# seletor.net
KiCad netlist of a schematic drawn in EAGLE
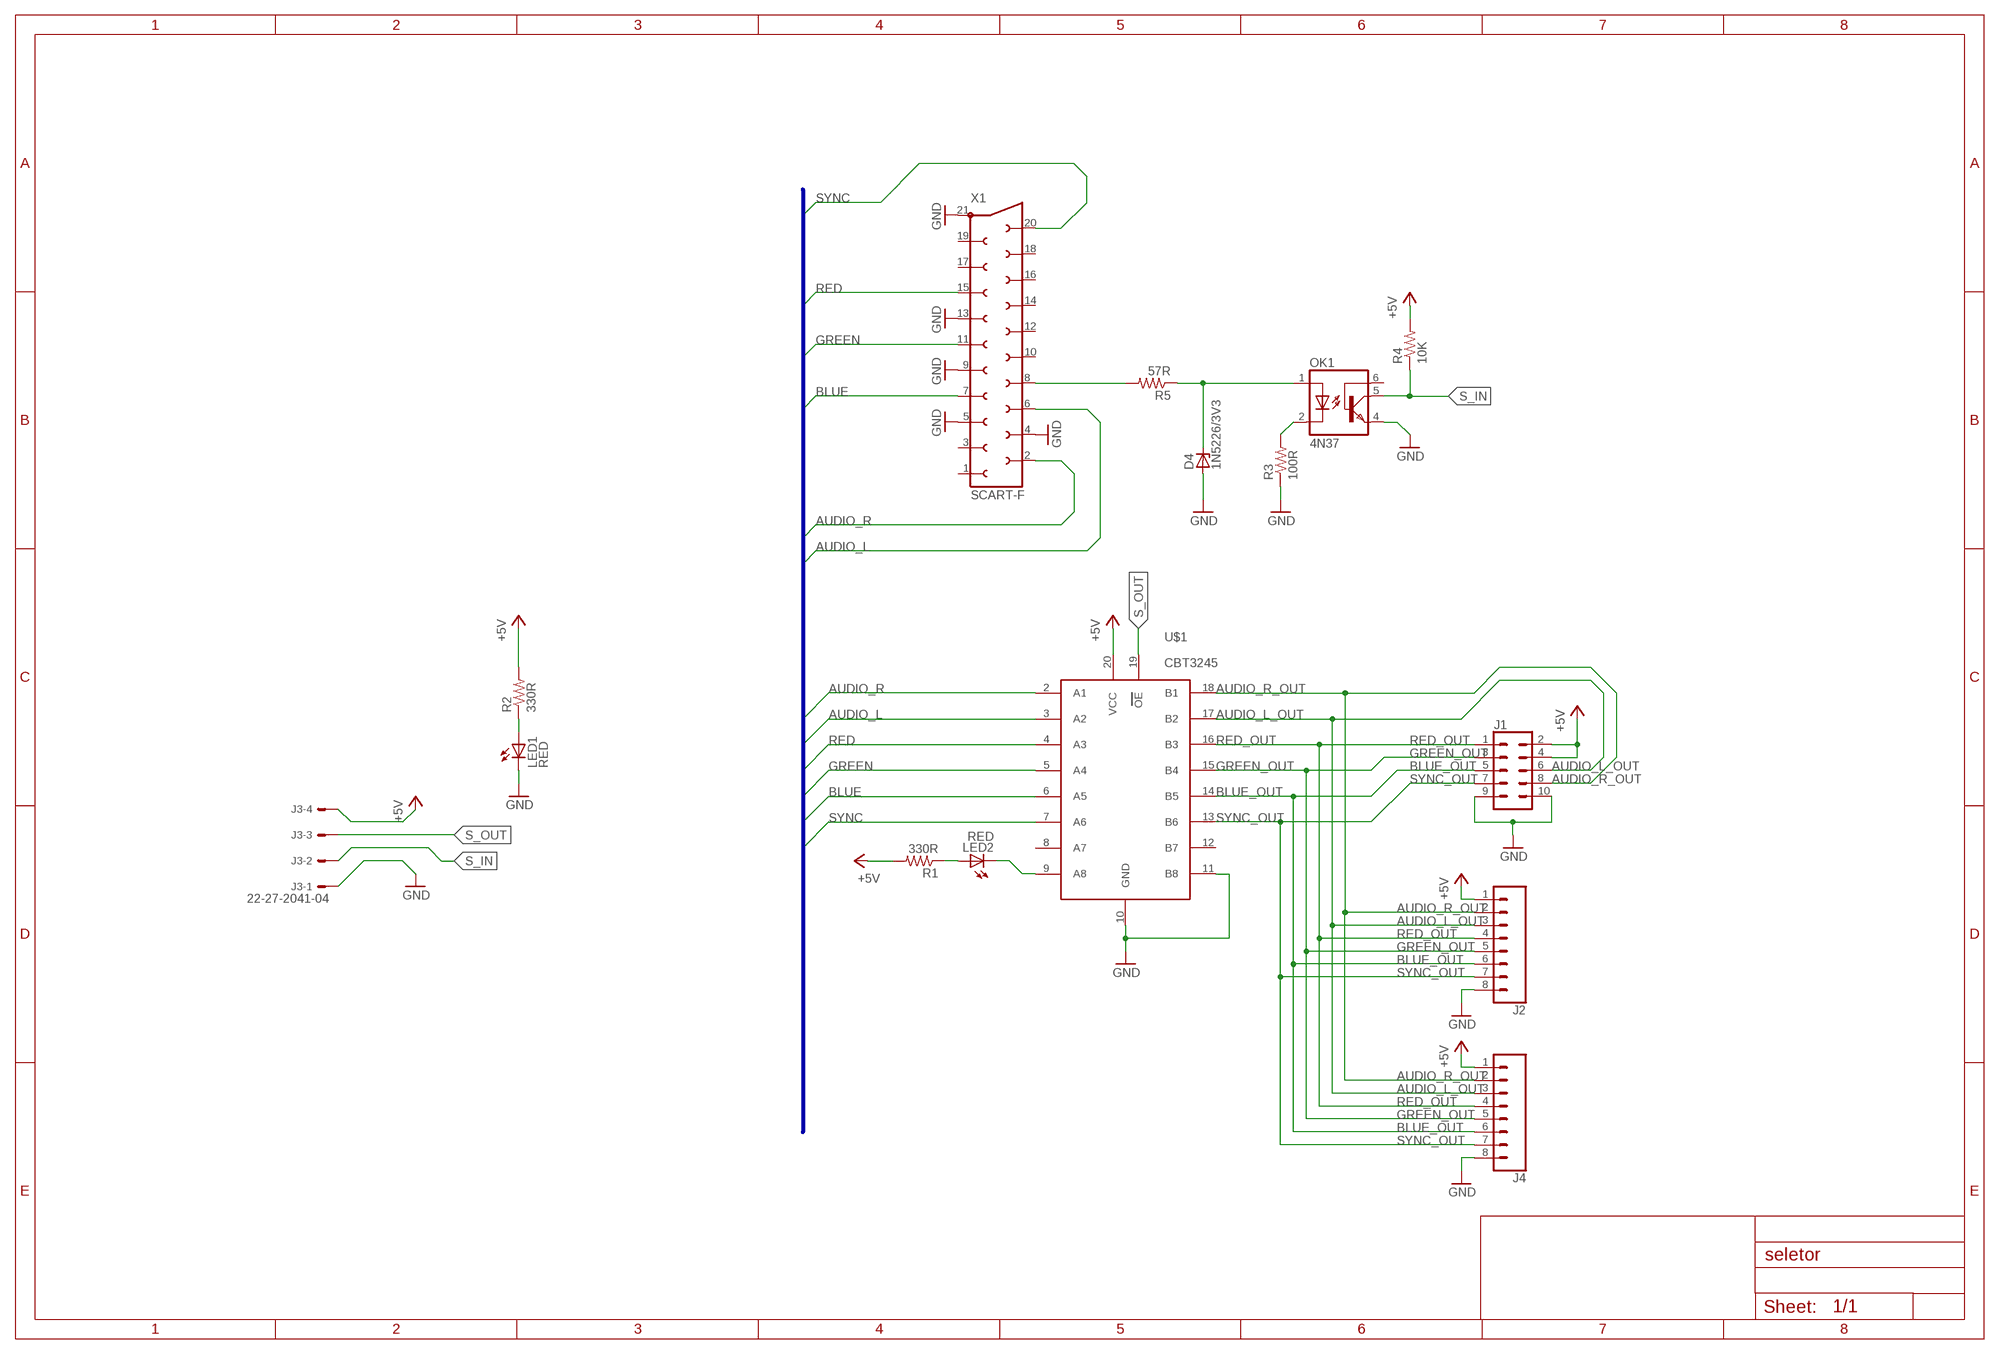
[diagram p0: schematic, sheet 1]

(export (version "E")
  (design (tool "Eeschema 10.0.6"))
  (components
    (comp (ref "D4")
      (value "1N5226/3V3")
      (footprint "eagle-import:DO34Z7")
      (libsource (lib "eagle-import") (part "BZX90"))
    )
    (comp (ref "J1")
      (value "CONN_05X2SHD")
      (footprint "eagle-import:2X5-SHROUDED")
      (libsource (lib "eagle-import") (part "CONN_05X2SHD"))
    )
    (comp (ref "J2")
      (value "CONN_08\"")
      (footprint "eagle-import:1X08")
      (libsource (lib "eagle-import") (part "CONN_08{dblquote}"))
    )
    (comp (ref "J3")
      (value "22-27-2041-04")
      (footprint "eagle-import:6410-04")
      (libsource (lib "eagle-import") (part "22-?-0427-2041"))
    )
    (comp (ref "J4")
      (value "CONN_08\"")
      (footprint "eagle-import:1X08")
      (libsource (lib "eagle-import") (part "CONN_08{dblquote}"))
    )
    (comp (ref "LED1")
      (value "RED")
      (footprint "eagle-import:LED5MM")
      (libsource (lib "eagle-import") (part "LED5MM"))
    )
    (comp (ref "LED2")
      (value "RED")
      (footprint "eagle-import:LED5MM")
      (libsource (lib "eagle-import") (part "LED5MM"))
    )
    (comp (ref "OK1")
      (value "4N37")
      (footprint "eagle-import:DIL06")
      (fields (field (name "MF") "FAIRCHILD SEMICONDUCTOR"))
      (libsource (lib "eagle-import") (part "4N37"))
    )
    (comp (ref "R1")
      (value "330R")
      (footprint "eagle-import:0204V")
      (libsource (lib "eagle-import") (part "R-US_0204/2V"))
    )
    (comp (ref "R2")
      (value "330R")
      (footprint "eagle-import:0204V")
      (libsource (lib "eagle-import") (part "R-US_0204/2V"))
    )
    (comp (ref "R3")
      (value "100R")
      (footprint "eagle-import:0204V")
      (libsource (lib "eagle-import") (part "R-US_0204/2V"))
    )
    (comp (ref "R4")
      (value "10K")
      (footprint "eagle-import:0204V")
      (libsource (lib "eagle-import") (part "R-US_0204/2V"))
    )
    (comp (ref "R5")
      (value "57R")
      (footprint "eagle-import:0204_7")
      (libsource (lib "eagle-import") (part "R-US_0204/7"))
    )
    (comp (ref "U$1")
      (value "CBT3245")
      (footprint "eagle-import:SO20")
      (libsource (lib "eagle-import") (part "CBT3245"))
    )
    (comp (ref "X1")
      (value "SCART-F")
      (footprint "eagle-import:SCART-F")
      (libsource (lib "eagle-import") (part "SCART-F"))
    )
  )
  (nets
    (net (code "1") (name "+5V") (class "Default")
      (node (ref "J1") (pin "2") (pinfunction "2_2") (pintype "passive"))
      (node (ref "J1") (pin "4") (pinfunction "4_4") (pintype "passive"))
      (node (ref "J2") (pin "1") (pinfunction "1_1") (pintype "passive"))
      (node (ref "J3") (pin "4") (pinfunction "S_4") (pintype "passive"))
      (node (ref "J4") (pin "1") (pinfunction "1_1") (pintype "passive"))
      (node (ref "R1") (pin "2") (pinfunction "2_2") (pintype "passive"))
      (node (ref "R2") (pin "2") (pinfunction "2_2") (pintype "passive"))
      (node (ref "R4") (pin "2") (pinfunction "2_2") (pintype "passive"))
      (node (ref "U$1") (pin "20") (pinfunction "VCC_20") (pintype "bidirectional"))
    )
    (net (code "2") (name "/AUDIO_L") (class "Default")
      (node (ref "U$1") (pin "3") (pinfunction "A2_3") (pintype "bidirectional"))
      (node (ref "X1") (pin "6") (pinfunction "6_6") (pintype "passive"))
    )
    (net (code "3") (name "/AUDIO_L_OUT") (class "Default")
      (node (ref "J1") (pin "6") (pinfunction "6_6") (pintype "passive"))
      (node (ref "J2") (pin "3") (pinfunction "3_3") (pintype "passive"))
      (node (ref "J4") (pin "3") (pinfunction "3_3") (pintype "passive"))
      (node (ref "U$1") (pin "17") (pinfunction "B2_17") (pintype "bidirectional"))
    )
    (net (code "4") (name "/AUDIO_R") (class "Default")
      (node (ref "U$1") (pin "2") (pinfunction "A1_2") (pintype "bidirectional"))
      (node (ref "X1") (pin "2") (pinfunction "2_2") (pintype "passive"))
    )
    (net (code "5") (name "/AUDIO_R_OUT") (class "Default")
      (node (ref "J1") (pin "8") (pinfunction "8_8") (pintype "passive"))
      (node (ref "J2") (pin "2") (pinfunction "2_2") (pintype "passive"))
      (node (ref "J4") (pin "2") (pinfunction "2_2") (pintype "passive"))
      (node (ref "U$1") (pin "18") (pinfunction "B1_18") (pintype "bidirectional"))
    )
    (net (code "6") (name "/BLUE") (class "Default")
      (node (ref "U$1") (pin "6") (pinfunction "A5_6") (pintype "bidirectional"))
      (node (ref "X1") (pin "7") (pinfunction "7_7") (pintype "passive"))
    )
    (net (code "7") (name "/BLUE_OUT") (class "Default")
      (node (ref "J1") (pin "5") (pinfunction "5_5") (pintype "passive"))
      (node (ref "J2") (pin "6") (pinfunction "6_6") (pintype "passive"))
      (node (ref "J4") (pin "6") (pinfunction "6_6") (pintype "passive"))
      (node (ref "U$1") (pin "14") (pinfunction "B5_14") (pintype "bidirectional"))
    )
    (net (code "8") (name "/GREEN") (class "Default")
      (node (ref "U$1") (pin "5") (pinfunction "A4_5") (pintype "bidirectional"))
      (node (ref "X1") (pin "11") (pinfunction "11_11") (pintype "passive"))
    )
    (net (code "9") (name "/GREEN_OUT") (class "Default")
      (node (ref "J1") (pin "3") (pinfunction "3_3") (pintype "passive"))
      (node (ref "J2") (pin "5") (pinfunction "5_5") (pintype "passive"))
      (node (ref "J4") (pin "5") (pinfunction "5_5") (pintype "passive"))
      (node (ref "U$1") (pin "15") (pinfunction "B4_15") (pintype "bidirectional"))
    )
    (net (code "10") (name "/RED") (class "Default")
      (node (ref "U$1") (pin "4") (pinfunction "A3_4") (pintype "bidirectional"))
      (node (ref "X1") (pin "15") (pinfunction "15_15") (pintype "passive"))
    )
    (net (code "11") (name "/RED_OUT") (class "Default")
      (node (ref "J1") (pin "1") (pinfunction "1_1") (pintype "passive"))
      (node (ref "J2") (pin "4") (pinfunction "4_4") (pintype "passive"))
      (node (ref "J4") (pin "4") (pinfunction "4_4") (pintype "passive"))
      (node (ref "U$1") (pin "16") (pinfunction "B3_16") (pintype "bidirectional"))
    )
    (net (code "12") (name "/SYNC") (class "Default")
      (node (ref "U$1") (pin "7") (pinfunction "A6_7") (pintype "bidirectional"))
      (node (ref "X1") (pin "20") (pinfunction "20_20") (pintype "passive"))
    )
    (net (code "13") (name "/SYNC_OUT") (class "Default")
      (node (ref "J1") (pin "7") (pinfunction "7_7") (pintype "passive"))
      (node (ref "J2") (pin "7") (pinfunction "7_7") (pintype "passive"))
      (node (ref "J4") (pin "7") (pinfunction "7_7") (pintype "passive"))
      (node (ref "U$1") (pin "13") (pinfunction "B6_13") (pintype "bidirectional"))
    )
    (net (code "14") (name "GND") (class "Default")
      (node (ref "D4") (pin "A") (pinfunction "A_A") (pintype "passive"))
      (node (ref "J1") (pin "10") (pinfunction "10_10") (pintype "passive"))
      (node (ref "J1") (pin "9") (pinfunction "9_9") (pintype "passive"))
      (node (ref "J2") (pin "8") (pinfunction "8_8") (pintype "passive"))
      (node (ref "J3") (pin "1") (pinfunction "S_1") (pintype "passive"))
      (node (ref "J4") (pin "8") (pinfunction "8_8") (pintype "passive"))
      (node (ref "LED1") (pin "K") (pinfunction "C_K") (pintype "passive"))
      (node (ref "OK1") (pin "4") (pinfunction "EMI_4") (pintype "passive"))
      (node (ref "R3") (pin "1") (pinfunction "1_1") (pintype "passive"))
      (node (ref "U$1") (pin "10") (pinfunction "GND_10") (pintype "bidirectional"))
      (node (ref "U$1") (pin "11") (pinfunction "B8_11") (pintype "bidirectional"))
      (node (ref "X1") (pin "13") (pinfunction "13_13") (pintype "passive"))
      (node (ref "X1") (pin "21") (pinfunction "21_21") (pintype "passive"))
      (node (ref "X1") (pin "4") (pinfunction "4_4") (pintype "passive"))
      (node (ref "X1") (pin "5") (pinfunction "5_5") (pintype "passive"))
      (node (ref "X1") (pin "9") (pinfunction "9_9") (pintype "passive"))
    )
    (net (code "15") (name "Net-(LED1-PadA)") (class "Default")
      (node (ref "LED1") (pin "A") (pinfunction "A_A") (pintype "passive"))
      (node (ref "R2") (pin "1") (pinfunction "1_1") (pintype "passive"))
    )
    (net (code "16") (name "Net-(LED2-C)") (class "Default")
      (node (ref "LED2") (pin "K") (pinfunction "C_K") (pintype "passive"))
      (node (ref "U$1") (pin "9") (pinfunction "A8_9") (pintype "bidirectional"))
    )
    (net (code "17") (name "Net-(LED2-PadA)") (class "Default")
      (node (ref "LED2") (pin "A") (pinfunction "A_A") (pintype "passive"))
      (node (ref "R1") (pin "1") (pinfunction "1_1") (pintype "passive"))
    )
    (net (code "18") (name "Net-(OK1-A)") (class "Default")
      (node (ref "D4") (pin "C") (pinfunction "C_C") (pintype "passive"))
      (node (ref "OK1") (pin "1") (pinfunction "A_1") (pintype "passive"))
      (node (ref "R5") (pin "1") (pinfunction "1_1") (pintype "passive"))
    )
    (net (code "19") (name "Net-(OK1-C)") (class "Default")
      (node (ref "OK1") (pin "2") (pinfunction "C_2") (pintype "passive"))
      (node (ref "R3") (pin "2") (pinfunction "2_2") (pintype "passive"))
    )
    (net (code "20") (name "Net-(R5-Pad2)") (class "Default")
      (node (ref "R5") (pin "2") (pinfunction "2_2") (pintype "passive"))
      (node (ref "X1") (pin "8") (pinfunction "8_8") (pintype "passive"))
    )
    (net (code "21") (name "S_IN") (class "Default")
      (node (ref "J3") (pin "2") (pinfunction "S_2") (pintype "passive"))
      (node (ref "OK1") (pin "5") (pinfunction "COL_5") (pintype "passive"))
      (node (ref "R4") (pin "1") (pinfunction "1_1") (pintype "passive"))
    )
    (net (code "22") (name "S_OUT") (class "Default")
      (node (ref "J3") (pin "3") (pinfunction "S_3") (pintype "passive"))
      (node (ref "U$1") (pin "19") (pinfunction "OE_19") (pintype "bidirectional"))
    )
    (net (code "23") (name "unconnected-(OK1-BAS-Pad6)") (class "Default")
      (node (ref "OK1") (pin "6") (pinfunction "BAS_6") (pintype "passive"))
    )
    (net (code "24") (name "unconnected-(U$1-A7-Pad8)") (class "Default")
      (node (ref "U$1") (pin "8") (pinfunction "A7_8") (pintype "bidirectional"))
    )
    (net (code "25") (name "unconnected-(U$1-B7-Pad12)") (class "Default")
      (node (ref "U$1") (pin "12") (pinfunction "B7_12") (pintype "bidirectional"))
    )
    (net (code "26") (name "unconnected-(X1-Pad1)") (class "Default")
      (node (ref "X1") (pin "1") (pinfunction "1_1") (pintype "passive"))
    )
    (net (code "27") (name "unconnected-(X1-Pad3)") (class "Default")
      (node (ref "X1") (pin "3") (pinfunction "3_3") (pintype "passive"))
    )
    (net (code "28") (name "unconnected-(X1-Pad10)") (class "Default")
      (node (ref "X1") (pin "10") (pinfunction "10_10") (pintype "passive"))
    )
    (net (code "29") (name "unconnected-(X1-Pad12)") (class "Default")
      (node (ref "X1") (pin "12") (pinfunction "12_12") (pintype "passive"))
    )
    (net (code "30") (name "unconnected-(X1-Pad14)") (class "Default")
      (node (ref "X1") (pin "14") (pinfunction "14_14") (pintype "passive"))
    )
    (net (code "31") (name "unconnected-(X1-Pad16)") (class "Default")
      (node (ref "X1") (pin "16") (pinfunction "16_16") (pintype "passive"))
    )
    (net (code "32") (name "unconnected-(X1-Pad17)") (class "Default")
      (node (ref "X1") (pin "17") (pinfunction "17_17") (pintype "passive"))
    )
    (net (code "33") (name "unconnected-(X1-Pad18)") (class "Default")
      (node (ref "X1") (pin "18") (pinfunction "18_18") (pintype "passive"))
    )
    (net (code "34") (name "unconnected-(X1-Pad19)") (class "Default")
      (node (ref "X1") (pin "19") (pinfunction "19_19") (pintype "passive"))
    )
  )
)
